# Display.net
KiCad netlist of a schematic drawn in Altium Designer
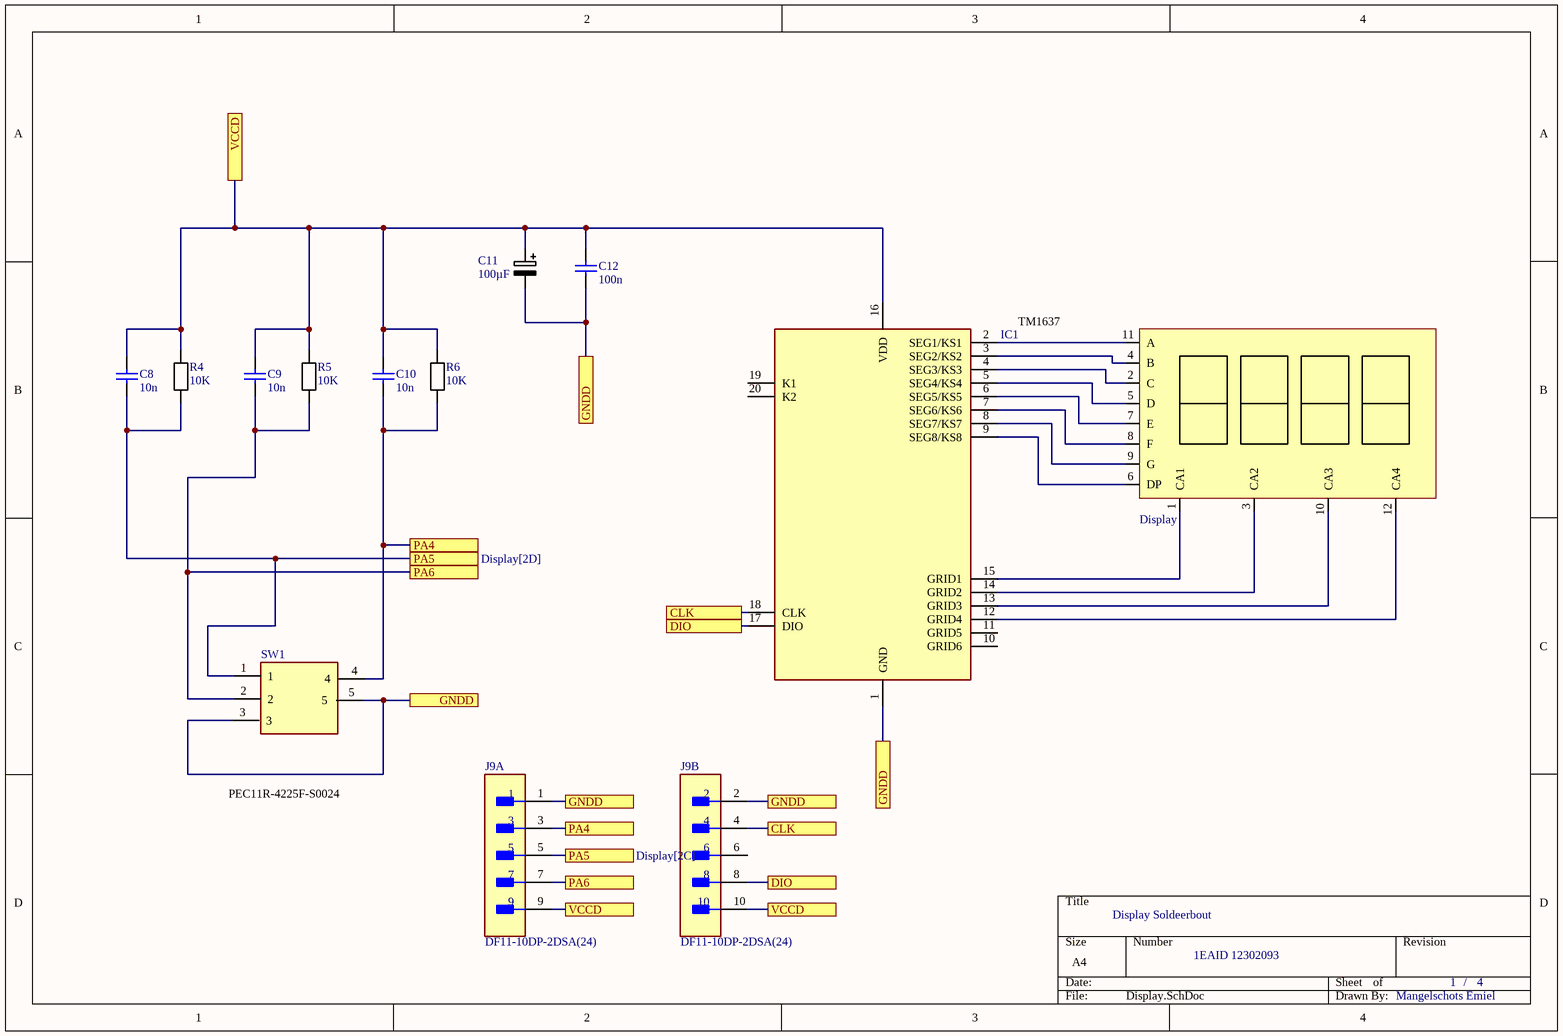
[diagram p0: Display.SchDoc]

(export (version "E")
  (design (tool "Eeschema 10.0.6"))
  (components
    (comp (ref "C8")
      (value "10n")
      (footprint "CAPA")
      (fields (field (name "PART NUMBER") "GRM1885C1H100JA01D") (field (name "MANUFACTURER") "Murata"))
      (libsource (lib "Schlib1") (part "Capasitor"))
    )
    (comp (ref "C9")
      (value "10n")
      (footprint "CAPA")
      (fields (field (name "PART NUMBER") "GRM1885C1H100JA01D") (field (name "MANUFACTURER") "Murata"))
      (libsource (lib "Schlib1") (part "Capasitor"))
    )
    (comp (ref "C10")
      (value "10n")
      (footprint "CAPA")
      (fields (field (name "PART NUMBER") "GRM1885C1H100JA01D") (field (name "MANUFACTURER") "Murata"))
      (libsource (lib "Schlib1") (part "Capasitor"))
    )
    (comp (ref "C11")
      (value "100µF")
      (footprint "CAPA1")
      (fields (field (name "PART NUMBER") "GRM1885C1H100JA01D") (field (name "MANUFACTURER") "Murata"))
      (libsource (lib "Schlib1") (part "Capasitor_1"))
    )
    (comp (ref "C12")
      (value "100n")
      (footprint "CAPA")
      (fields (field (name "PART NUMBER") "GRM1885C1H100JA01D") (field (name "MANUFACTURER") "Murata"))
      (libsource (lib "Schlib1") (part "Capasitor"))
    )
    (comp (ref "IC8")
      (value "IC1")
      (footprint "DIP778W43P254L2612H431Q20N")
      (description "TM1637")
      (libsource (lib "Schlib1") (part "IC1"))
    )
    (comp (ref "J9")
      (value "DF11-10DP-2DSA(24)")
      (footprint "FP-DF11-10DP-2DSA_24-MFG")
      (description "CONN HEADER VERT 10POS 2MM")
      (fields
        (field (name "OCTOPART") "https://octopart.com/df11-10dp-2dsa%2824%29-hirose-39521433")
        (field (name "MANUFACTURER") "Hirose")
      )
      (libsource (lib "Schlib1") (part "CMP-11610-000008-1"))
    )
    (comp (ref "KW4-801AVB")
      (value "Display")
      (footprint "DISP")
      (description "KW4-801AVB")
      (libsource (lib "Schlib1") (part "Display"))
    )
    (comp (ref "R4")
      (value "10K")
      (footprint "REST")
      (fields (field (name "MANUFACTURER") "Vishay Dale") (field (name "PART NUMBER") "CRCW08050000Z0EA"))
      (libsource (lib "Schlib1") (part "resistor"))
    )
    (comp (ref "R5")
      (value "10K")
      (footprint "REST")
      (fields (field (name "MANUFACTURER") "Vishay Dale") (field (name "PART NUMBER") "CRCW08050000Z0EA"))
      (libsource (lib "Schlib1") (part "resistor"))
    )
    (comp (ref "R6")
      (value "10K")
      (footprint "REST")
      (fields (field (name "MANUFACTURER") "Vishay Dale") (field (name "PART NUMBER") "CRCW08050000Z0EA"))
      (libsource (lib "Schlib1") (part "resistor"))
    )
    (comp (ref "SW1")
      (value "SW1")
      (footprint "SW1")
      (description "PEC11R-4225F-S0024")
      (libsource (lib "Schlib1") (part "SW1"))
    )
  )
  (nets
    (net (code "1") (name "/CLK") (class "Default")
      (node (ref "IC8") (pin "18") (pinfunction "CLK_18") (pintype "passive"))
      (node (ref "J9") (pin "4") (pinfunction "4_4") (pintype "passive"))
    )
    (net (code "2") (name "/DIO") (class "Default")
      (node (ref "IC8") (pin "17") (pinfunction "DIO_17") (pintype "passive"))
      (node (ref "J9") (pin "8") (pinfunction "8_8") (pintype "passive"))
    )
    (net (code "3") (name "/GNDD") (class "Default")
      (node (ref "C11") (pin "2") (pinfunction "2_2") (pintype "passive"))
      (node (ref "C12") (pin "1") (pinfunction "1_1") (pintype "passive"))
      (node (ref "IC8") (pin "1") (pinfunction "GND_1") (pintype "passive"))
      (node (ref "J9") (pin "1") (pinfunction "1_1") (pintype "passive"))
      (node (ref "J9") (pin "2") (pinfunction "2_2") (pintype "passive"))
      (node (ref "SW1") (pin "3") (pinfunction "3_3") (pintype "passive"))
      (node (ref "SW1") (pin "5") (pinfunction "5_5") (pintype "passive"))
    )
    (net (code "4") (name "/PA4") (class "Default")
      (node (ref "C10") (pin "1") (pinfunction "1_1") (pintype "passive"))
      (node (ref "J9") (pin "3") (pinfunction "3_3") (pintype "passive"))
      (node (ref "R6") (pin "1") (pinfunction "1_1") (pintype "passive"))
      (node (ref "SW1") (pin "4") (pinfunction "4_4") (pintype "passive"))
    )
    (net (code "5") (name "/PA5") (class "Default")
      (node (ref "C8") (pin "1") (pinfunction "1_1") (pintype "passive"))
      (node (ref "J9") (pin "5") (pinfunction "5_5") (pintype "passive"))
      (node (ref "R4") (pin "1") (pinfunction "1_1") (pintype "passive"))
      (node (ref "SW1") (pin "1") (pinfunction "1_1") (pintype "passive"))
    )
    (net (code "6") (name "/PA6") (class "Default")
      (node (ref "C9") (pin "1") (pinfunction "1_1") (pintype "passive"))
      (node (ref "J9") (pin "7") (pinfunction "7_7") (pintype "passive"))
      (node (ref "R5") (pin "1") (pinfunction "1_1") (pintype "passive"))
      (node (ref "SW1") (pin "2") (pinfunction "2_2") (pintype "passive"))
    )
    (net (code "7") (name "/VCCD") (class "Default")
      (node (ref "C10") (pin "2") (pinfunction "2_2") (pintype "passive"))
      (node (ref "C11") (pin "1") (pinfunction "1_1") (pintype "passive"))
      (node (ref "C12") (pin "2") (pinfunction "2_2") (pintype "passive"))
      (node (ref "C8") (pin "2") (pinfunction "2_2") (pintype "passive"))
      (node (ref "C9") (pin "2") (pinfunction "2_2") (pintype "passive"))
      (node (ref "IC8") (pin "16") (pinfunction "VDD_16") (pintype "passive"))
      (node (ref "J9") (pin "10") (pinfunction "10_10") (pintype "passive"))
      (node (ref "J9") (pin "9") (pinfunction "9_9") (pintype "passive"))
      (node (ref "R4") (pin "2") (pinfunction "2_2") (pintype "passive"))
      (node (ref "R5") (pin "2") (pinfunction "2_2") (pintype "passive"))
      (node (ref "R6") (pin "2") (pinfunction "2_2") (pintype "passive"))
    )
    (net (code "8") (name "Net-(IC8-GRID1)") (class "Default")
      (node (ref "IC8") (pin "15") (pinfunction "GRID1_15") (pintype "passive"))
      (node (ref "KW4-801AVB") (pin "1") (pinfunction "CA1_1") (pintype "passive"))
    )
    (net (code "9") (name "Net-(IC8-GRID2)") (class "Default")
      (node (ref "IC8") (pin "14") (pinfunction "GRID2_14") (pintype "passive"))
      (node (ref "KW4-801AVB") (pin "3") (pinfunction "CA2_3") (pintype "passive"))
    )
    (net (code "10") (name "Net-(IC8-GRID3)") (class "Default")
      (node (ref "IC8") (pin "13") (pinfunction "GRID3_13") (pintype "passive"))
      (node (ref "KW4-801AVB") (pin "10") (pinfunction "CA3_10") (pintype "passive"))
    )
    (net (code "11") (name "Net-(IC8-GRID4)") (class "Default")
      (node (ref "IC8") (pin "12") (pinfunction "GRID4_12") (pintype "passive"))
      (node (ref "KW4-801AVB") (pin "12") (pinfunction "CA4_12") (pintype "passive"))
    )
    (net (code "12") (name "Net-(IC8-SEG1{slash}KS1)") (class "Default")
      (node (ref "IC8") (pin "2") (pinfunction "SEG1/KS1_2") (pintype "passive"))
      (node (ref "KW4-801AVB") (pin "11") (pinfunction "A_11") (pintype "passive"))
    )
    (net (code "13") (name "Net-(IC8-SEG2{slash}KS2)") (class "Default")
      (node (ref "IC8") (pin "3") (pinfunction "SEG2/KS2_3") (pintype "passive"))
      (node (ref "KW4-801AVB") (pin "4") (pinfunction "B_4") (pintype "passive"))
    )
    (net (code "14") (name "Net-(IC8-SEG3{slash}KS3)") (class "Default")
      (node (ref "IC8") (pin "4") (pinfunction "SEG3/KS3_4") (pintype "passive"))
      (node (ref "KW4-801AVB") (pin "2") (pinfunction "C_2") (pintype "passive"))
    )
    (net (code "15") (name "Net-(IC8-SEG4{slash}KS4)") (class "Default")
      (node (ref "IC8") (pin "5") (pinfunction "SEG4/KS4_5") (pintype "passive"))
      (node (ref "KW4-801AVB") (pin "5") (pinfunction "D_5") (pintype "passive"))
    )
    (net (code "16") (name "Net-(IC8-SEG5{slash}KS5)") (class "Default")
      (node (ref "IC8") (pin "6") (pinfunction "SEG5/KS5_6") (pintype "passive"))
      (node (ref "KW4-801AVB") (pin "7") (pinfunction "E_7") (pintype "passive"))
    )
    (net (code "17") (name "Net-(IC8-SEG6{slash}KS6)") (class "Default")
      (node (ref "IC8") (pin "7") (pinfunction "SEG6/KS6_7") (pintype "passive"))
      (node (ref "KW4-801AVB") (pin "8") (pinfunction "F_8") (pintype "passive"))
    )
    (net (code "18") (name "Net-(IC8-SEG7{slash}KS7)") (class "Default")
      (node (ref "IC8") (pin "8") (pinfunction "SEG7/KS7_8") (pintype "passive"))
      (node (ref "KW4-801AVB") (pin "9") (pinfunction "G_9") (pintype "passive"))
    )
    (net (code "19") (name "Net-(IC8-SEG8{slash}KS8)") (class "Default")
      (node (ref "IC8") (pin "9") (pinfunction "SEG8/KS8_9") (pintype "passive"))
      (node (ref "KW4-801AVB") (pin "6") (pinfunction "DP_6") (pintype "passive"))
    )
    (net (code "20") (name "unconnected-(IC8-GRID5-Pad11)") (class "Default")
      (node (ref "IC8") (pin "11") (pinfunction "GRID5_11") (pintype "passive"))
    )
    (net (code "21") (name "unconnected-(IC8-GRID6-Pad10)") (class "Default")
      (node (ref "IC8") (pin "10") (pinfunction "GRID6_10") (pintype "passive"))
    )
    (net (code "22") (name "unconnected-(IC8-K1-Pad19)") (class "Default")
      (node (ref "IC8") (pin "19") (pinfunction "K1_19") (pintype "passive"))
    )
    (net (code "23") (name "unconnected-(IC8-K2-Pad20)") (class "Default")
      (node (ref "IC8") (pin "20") (pinfunction "K2_20") (pintype "passive"))
    )
    (net (code "24") (name "unconnected-(J9-Pad6)") (class "Default")
      (node (ref "J9") (pin "6") (pinfunction "6_6") (pintype "passive"))
    )
  )
)
